# Funk.net
KiCad netlist of a schematic drawn in Altium Designer
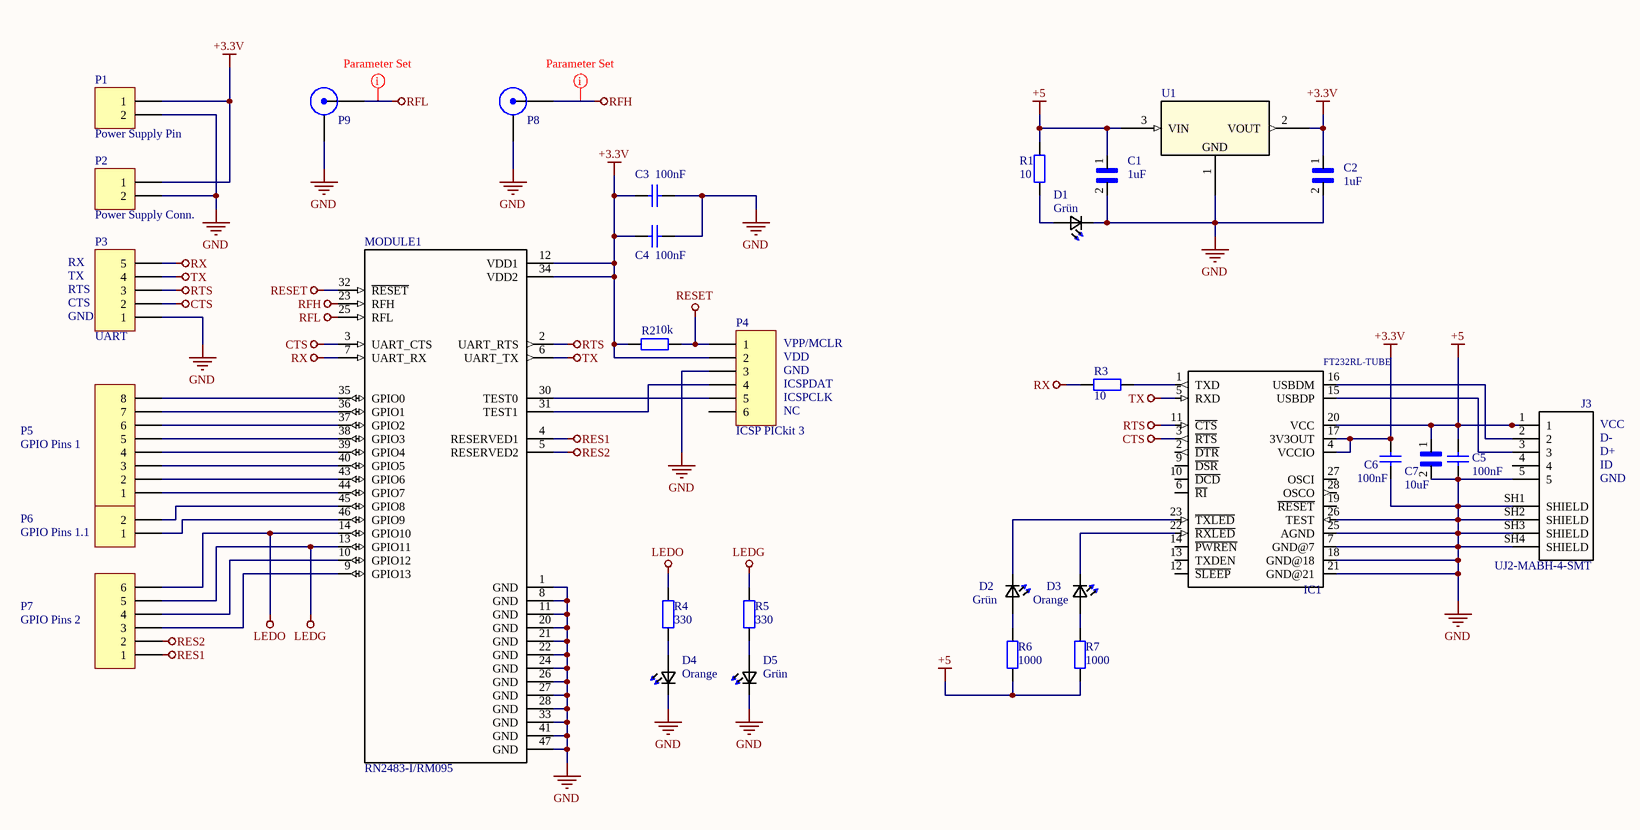
[diagram p0: Funk.SchDoc]

(export (version "E")
  (design (tool "Eeschema 10.0.6"))
  (components
    (comp (ref "C1")
      (value "1uF")
      (footprint "*CAPC2012X135N")
      (fields
        (field (name "DIGI-KEY_PART_NUMBER") "1276-6456-1-ND")
        (field (name "MP") "CL21A106KPFNNNG")
        (field (name "MF") "Samsung Electro-Mechanics")
      )
      (libsource (lib "Funk") (part "CL21A106KPFNNNG"))
    )
    (comp (ref "C2")
      (value "1uF")
      (footprint "*CAPC2012X135N")
      (fields
        (field (name "DIGI-KEY_PART_NUMBER") "1276-6456-1-ND")
        (field (name "MP") "CL21A106KPFNNNG")
        (field (name "MF") "Samsung Electro-Mechanics")
      )
      (libsource (lib "Funk") (part "CL21A106KPFNNNG"))
    )
    (comp (ref "C3")
      (value "100nF")
      (footprint "CAP_0603i_1608m -L")
      (description "capacitor")
      (libsource (lib "IDSC std generic parts") (part "Cap"))
    )
    (comp (ref "C4")
      (value "100nF")
      (footprint "CAP_0603i_1608m -L")
      (description "capacitor")
      (libsource (lib "IDSC std generic parts") (part "Cap"))
    )
    (comp (ref "C5")
      (value "100nF")
      (footprint "CAP_0603i_1608m -L")
      (description "capacitor")
      (libsource (lib "IDSC std generic parts") (part "Cap"))
    )
    (comp (ref "C6")
      (value "100nF")
      (footprint "CAP_0603i_1608m -L")
      (description "capacitor")
      (libsource (lib "IDSC std generic parts") (part "Cap"))
    )
    (comp (ref "C7")
      (value "10uF")
      (footprint "*CAPC2012X135N")
      (fields
        (field (name "DIGI-KEY_PART_NUMBER") "1276-6456-1-ND")
        (field (name "MP") "CL21A106KPFNNNG")
        (field (name "MF") "Samsung Electro-Mechanics")
      )
      (libsource (lib "Funk") (part "CL21A106KPFNNNG"))
    )
    (comp (ref "D1")
      (value "Grün")
      (footprint "*0603")
      (description "LED; SMD; 0603; gr黱; 35mcd; 1.6x0.8x0.55mm; 130掳; 2梅2.V; 20mA")
      (fields (field (name "MP") "LTST-C191KGKT") (field (name "DIGI-KEY_PART_NUMBER") "160-1446-1-ND"))
      (libsource (lib "Funk") (part "LTST-C191KGKT"))
    )
    (comp (ref "D2")
      (value "Grün")
      (footprint "*0603")
      (description "LED; SMD; 0603; gr黱; 35mcd; 1.6x0.8x0.55mm; 130掳; 2梅2.V; 20mA")
      (fields (field (name "MP") "LTST-C191KGKT") (field (name "DIGI-KEY_PART_NUMBER") "160-1446-1-ND"))
      (libsource (lib "Funk") (part "LTST-C191KGKT"))
    )
    (comp (ref "D3")
      (value "Orange")
      (footprint "*0603")
      (description "LED; SMD; 0603; orange; 45-90mcd; 1.6x0.8x0.55mm; 130Â°; 2Ã·2.4V; 20mA")
      (fields (field (name "MP") "LTST-C191KFKT") (field (name "DIGI-KEY_PART_NUMBER") "160-1445-1-ND"))
      (libsource (lib "Funk") (part "LTST-C191KFKT"))
    )
    (comp (ref "D4")
      (value "Orange")
      (footprint "*0603")
      (description "LED; SMD; 0603; orange; 45-90mcd; 1.6x0.8x0.55mm; 130Â°; 2Ã·2.4V; 20mA")
      (fields (field (name "MP") "LTST-C191KFKT") (field (name "DIGI-KEY_PART_NUMBER") "160-1445-1-ND"))
      (libsource (lib "Funk") (part "LTST-C191KFKT"))
    )
    (comp (ref "D5")
      (value "Grün")
      (footprint "*0603")
      (description "LED; SMD; 0603; gr黱; 35mcd; 1.6x0.8x0.55mm; 130掳; 2梅2.V; 20mA")
      (fields (field (name "MP") "LTST-C191KGKT") (field (name "DIGI-KEY_PART_NUMBER") "160-1446-1-ND"))
      (libsource (lib "Funk") (part "LTST-C191KGKT"))
    )
    (comp (ref "IC1")
      (value "FT232RL-TUBE")
      (footprint "*SSOP28-LD")
      (description "USB-to-UART 1-CH 256byte FIFO 5V 28-Pin SSOP Tube")
      (fields (field (name "DIGI-KEY_PART_NUMBER") "768-1306-ND") (field (name "MF") "FTDI,"))
      (libsource (lib "Funk") (part "FT232RL-TUBE"))
    )
    (comp (ref "J3")
      (value "UJ2-MABH-4-SMT")
      (footprint "*CUI_UJ2-MABH-4-SMT_UJ2-MABH-4-SMT(Primary)")
      (description "Mini AB, USB 2.0, 1 A, Right Angle, Surface Mount _SMT_, USB Receptacle")
      (fields (field (name "DIGI-KEY_PART_NUMBER") "102-5890-1-ND") (field (name "MF") "CUI Inc."))
      (libsource (lib "Funk") (part "UJ2-MABH-4-SMT"))
    )
    (comp (ref "MODULE1")
      (value "RN2483-I/RM095")
      (footprint "*MICROCHIP_RN2483-I/RM095")
      (description "Sub-GHz Dual Band Long Range Transceiver LoRa Module")
      (fields (field (name "MF") "Microchip"))
      (libsource (lib "Funk") (part "RN2483-I/RM095"))
    )
    (comp (ref "P1")
      (value "Power Supply Pin")
      (footprint "HDR1X2")
      (description "Header, 2-Pin")
      (libsource (lib "") (part "Header 2_1"))
    )
    (comp (ref "P2")
      (value "Power Supply Conn.")
      (footprint "3.5MM Phoenix Contact 1984617")
      (description "Header, 2-Pin")
      (libsource (lib "") (part "Header 2_1"))
    )
    (comp (ref "P3")
      (value "UART")
      (footprint "HDR1X5")
      (description "Header, 5-Pin")
      (libsource (lib "IDSC std connectors") (part "Header 5"))
    )
    (comp (ref "P4")
      (value "ICSP PICkit 3")
      (footprint "HDR1X6")
      (description "Header, 6-Pin")
      (libsource (lib "") (part "Header 6_1"))
    )
    (comp (ref "P5")
      (value "GPIO Pins 1")
      (footprint "HDR1X8")
      (description "Header, 8-Pin")
      (libsource (lib "IDSC std connectors") (part "Header 8"))
    )
    (comp (ref "P6")
      (value "GPIO Pins 1.1")
      (footprint "HDR1X2")
      (description "Header, 2-Pin")
      (libsource (lib "IDSC std connectors") (part "Header 2"))
    )
    (comp (ref "P7")
      (value "GPIO Pins 2")
      (footprint "HDR1X6")
      (description "Header, 6-Pin")
      (libsource (lib "IDSC std connectors") (part "Header 6"))
    )
    (comp (ref "P8")
      (value "Hirose U.FL-R-SMT-1(10)")
      (footprint "Hirsoe U.FL-R-SMT-1(10)")
      (description "U.FL")
      (libsource (lib "IDSC std connectors") (part "Hirose U.FL-R-SMT-1(10)"))
    )
    (comp (ref "P9")
      (value "Hirose U.FL-R-SMT-1(10)")
      (footprint "Hirsoe U.FL-R-SMT-1(10)")
      (description "U.FL")
      (libsource (lib "IDSC std connectors") (part "Hirose U.FL-R-SMT-1(10)"))
    )
    (comp (ref "R1")
      (value "10")
      (footprint "RES_0603i_1608m -N")
      (description "Resistor")
      (libsource (lib "") (part "Res_2"))
    )
    (comp (ref "R2")
      (value "10k")
      (footprint "RES_0603_1608m -L")
      (description "Resistor")
      (libsource (lib "") (part "Res_1"))
    )
    (comp (ref "R3")
      (value "10")
      (footprint "RES_0603i_1608m -N")
      (description "Resistor")
      (libsource (lib "") (part "Res_3"))
    )
    (comp (ref "R4")
      (value "330")
      (footprint "RES_0603i_1608m -N")
      (description "Resistor")
      (libsource (lib "IDSC std generic parts") (part "Res"))
    )
    (comp (ref "R5")
      (value "330")
      (footprint "RES_0603i_1608m -N")
      (description "Resistor")
      (libsource (lib "IDSC std generic parts") (part "Res"))
    )
    (comp (ref "R6")
      (value "1000")
      (footprint "RES_0603i_1608m -N")
      (description "Resistor")
      (libsource (lib "IDSC std generic parts") (part "Res"))
    )
    (comp (ref "R7")
      (value "1000")
      (footprint "RES_0603i_1608m -N")
      (description "Resistor")
      (libsource (lib "IDSC std generic parts") (part "Res"))
    )
    (comp (ref "U1")
      (value "Part Number: AP2120N-3.3TRG1")
      (footprint "SOT-23-M")
      (description "No Description Available")
      (fields
        (field (name "MANUFACTURER_PART_NUMBER") "AP2120N-3.3TRG1")
        (field (name "COPYRIGHT") "Copyright (C) 2018 Accelerated Designs. All rights reserved")
      )
      (libsource (lib "Funk") (part "AP2120N-3.3TRG1"))
    )
  )
  (nets
    (net (code "1") (name "+3.3V") (class "Default")
      (node (ref "C2") (pin "1") (pinfunction "1_1") (pintype "passive"))
      (node (ref "C3") (pin "2") (pinfunction "2_2") (pintype "passive"))
      (node (ref "C4") (pin "2") (pinfunction "2_2") (pintype "passive"))
      (node (ref "C6") (pin "2") (pinfunction "2_2") (pintype "passive"))
      (node (ref "IC1") (pin "17") (pinfunction "3V3OUT_17") (pintype "power_in"))
      (node (ref "IC1") (pin "4") (pinfunction "VCCIO_4") (pintype "power_in"))
      (node (ref "MODULE1") (pin "12") (pinfunction "VDD1_12") (pintype "power_in"))
      (node (ref "MODULE1") (pin "34") (pinfunction "VDD2_34") (pintype "power_in"))
      (node (ref "P1") (pin "1") (pinfunction "1_1") (pintype "passive"))
      (node (ref "P2") (pin "1") (pinfunction "1_1") (pintype "passive"))
      (node (ref "P4") (pin "2") (pinfunction "2_2") (pintype "passive"))
      (node (ref "R2") (pin "1") (pinfunction "1_1") (pintype "passive"))
      (node (ref "U1") (pin "2") (pinfunction "VOUT_2") (pintype "output"))
    )
    (net (code "2") (name "+5") (class "Default")
      (node (ref "C1") (pin "1") (pinfunction "1_1") (pintype "passive"))
      (node (ref "C5") (pin "2") (pinfunction "2_2") (pintype "passive"))
      (node (ref "C7") (pin "1") (pinfunction "1_1") (pintype "passive"))
      (node (ref "IC1") (pin "20") (pinfunction "VCC_20") (pintype "power_in"))
      (node (ref "J3") (pin "1") (pinfunction "1_1") (pintype "passive"))
      (node (ref "R1") (pin "1") (pinfunction "1_1") (pintype "passive"))
      (node (ref "R6") (pin "1") (pinfunction "1_1") (pintype "passive"))
      (node (ref "R7") (pin "1") (pinfunction "1_1") (pintype "passive"))
      (node (ref "U1") (pin "3") (pinfunction "VIN_3") (pintype "input"))
    )
    (net (code "3") (name "CTS") (class "Default")
      (node (ref "IC1") (pin "3") (pinfunction "~{RTS}_3") (pintype "output"))
      (node (ref "MODULE1") (pin "3") (pinfunction "UART_CTS_3") (pintype "input"))
      (node (ref "P3") (pin "2") (pinfunction "2_2") (pintype "passive"))
    )
    (net (code "4") (name "GND") (class "Default")
      (node (ref "C1") (pin "2") (pinfunction "2_2") (pintype "passive"))
      (node (ref "C2") (pin "2") (pinfunction "2_2") (pintype "passive"))
      (node (ref "C3") (pin "1") (pinfunction "1_1") (pintype "passive"))
      (node (ref "C4") (pin "1") (pinfunction "1_1") (pintype "passive"))
      (node (ref "C5") (pin "1") (pinfunction "1_1") (pintype "passive"))
      (node (ref "C6") (pin "1") (pinfunction "1_1") (pintype "passive"))
      (node (ref "C7") (pin "2") (pinfunction "2_2") (pintype "passive"))
      (node (ref "D1") (pin "1") (pinfunction "K2_1") (pintype "passive"))
      (node (ref "D4") (pin "1") (pinfunction "K2_1") (pintype "passive"))
      (node (ref "D5") (pin "1") (pinfunction "K2_1") (pintype "passive"))
      (node (ref "IC1") (pin "18") (pinfunction "GND@18_18") (pintype "power_in"))
      (node (ref "IC1") (pin "21") (pinfunction "GND@21_21") (pintype "power_in"))
      (node (ref "IC1") (pin "25") (pinfunction "AGND_25") (pintype "power_in"))
      (node (ref "IC1") (pin "26") (pinfunction "TEST_26") (pintype "input"))
      (node (ref "IC1") (pin "7") (pinfunction "GND@7_7") (pintype "power_in"))
      (node (ref "J3") (pin "5") (pinfunction "5_5") (pintype "passive"))
      (node (ref "J3") (pin "SH1") (pinfunction "SHIELD_SH1") (pintype "passive"))
      (node (ref "J3") (pin "SH2") (pinfunction "SHIELD_SH2") (pintype "passive"))
      (node (ref "J3") (pin "SH3") (pinfunction "SHIELD_SH3") (pintype "passive"))
      (node (ref "J3") (pin "SH4") (pinfunction "SHIELD_SH4") (pintype "passive"))
      (node (ref "MODULE1") (pin "1") (pinfunction "GND_1") (pintype "passive"))
      (node (ref "MODULE1") (pin "11") (pinfunction "GND_11") (pintype "passive"))
      (node (ref "MODULE1") (pin "20") (pinfunction "GND_20") (pintype "passive"))
      (node (ref "MODULE1") (pin "21") (pinfunction "GND_21") (pintype "passive"))
      (node (ref "MODULE1") (pin "22") (pinfunction "GND_22") (pintype "passive"))
      (node (ref "MODULE1") (pin "24") (pinfunction "GND_24") (pintype "passive"))
      (node (ref "MODULE1") (pin "26") (pinfunction "GND_26") (pintype "passive"))
      (node (ref "MODULE1") (pin "27") (pinfunction "GND_27") (pintype "passive"))
      (node (ref "MODULE1") (pin "28") (pinfunction "GND_28") (pintype "passive"))
      (node (ref "MODULE1") (pin "33") (pinfunction "GND_33") (pintype "passive"))
      (node (ref "MODULE1") (pin "41") (pinfunction "GND_41") (pintype "passive"))
      (node (ref "MODULE1") (pin "47") (pinfunction "GND_47") (pintype "passive"))
      (node (ref "MODULE1") (pin "8") (pinfunction "GND_8") (pintype "passive"))
      (node (ref "P1") (pin "2") (pinfunction "2_2") (pintype "passive"))
      (node (ref "P2") (pin "2") (pinfunction "2_2") (pintype "passive"))
      (node (ref "P3") (pin "1") (pinfunction "1_1") (pintype "passive"))
      (node (ref "P4") (pin "3") (pinfunction "3_3") (pintype "passive"))
      (node (ref "P8") (pin "2") (pinfunction "2_2") (pintype "passive"))
      (node (ref "P9") (pin "2") (pinfunction "2_2") (pintype "passive"))
      (node (ref "U1") (pin "1") (pinfunction "GND_1") (pintype "power_in"))
    )
    (net (code "5") (name "LEDG") (class "Default")
      (node (ref "MODULE1") (pin "13") (pinfunction "GPIO11_13") (pintype "bidirectional"))
      (node (ref "P7") (pin "5") (pinfunction "5_5") (pintype "passive"))
      (node (ref "R5") (pin "2") (pinfunction "2_2") (pintype "passive"))
    )
    (net (code "6") (name "LEDO") (class "Default")
      (node (ref "MODULE1") (pin "14") (pinfunction "GPIO10_14") (pintype "bidirectional"))
      (node (ref "P7") (pin "6") (pinfunction "6_6") (pintype "passive"))
      (node (ref "R4") (pin "2") (pinfunction "2_2") (pintype "passive"))
    )
    (net (code "7") (name "Net-(D1-A2)") (class "Default")
      (node (ref "D1") (pin "2") (pinfunction "A2_2") (pintype "passive"))
      (node (ref "R1") (pin "2") (pinfunction "2_2") (pintype "passive"))
    )
    (net (code "8") (name "Net-(D2-A2)") (class "Default")
      (node (ref "D2") (pin "2") (pinfunction "A2_2") (pintype "passive"))
      (node (ref "R6") (pin "2") (pinfunction "2_2") (pintype "passive"))
    )
    (net (code "9") (name "Net-(D2-K2)") (class "Default")
      (node (ref "D2") (pin "1") (pinfunction "K2_1") (pintype "passive"))
      (node (ref "IC1") (pin "23") (pinfunction "~{TXLED}_23") (pintype "input"))
    )
    (net (code "10") (name "Net-(D3-A2)") (class "Default")
      (node (ref "D3") (pin "2") (pinfunction "A2_2") (pintype "passive"))
      (node (ref "R7") (pin "2") (pinfunction "2_2") (pintype "passive"))
    )
    (net (code "11") (name "Net-(D3-K2)") (class "Default")
      (node (ref "D3") (pin "1") (pinfunction "K2_1") (pintype "passive"))
      (node (ref "IC1") (pin "22") (pinfunction "~{RXLED}_22") (pintype "input"))
    )
    (net (code "12") (name "Net-(D4-A2)") (class "Default")
      (node (ref "D4") (pin "2") (pinfunction "A2_2") (pintype "passive"))
      (node (ref "R4") (pin "1") (pinfunction "1_1") (pintype "passive"))
    )
    (net (code "13") (name "Net-(D5-A2)") (class "Default")
      (node (ref "D5") (pin "2") (pinfunction "A2_2") (pintype "passive"))
      (node (ref "R5") (pin "1") (pinfunction "1_1") (pintype "passive"))
    )
    (net (code "14") (name "Net-(IC1-TXD)") (class "Default")
      (node (ref "IC1") (pin "1") (pinfunction "TXD_1") (pintype "output"))
      (node (ref "R3") (pin "1") (pinfunction "1_1") (pintype "passive"))
    )
    (net (code "15") (name "Net-(IC1-USBDM)") (class "Default")
      (node (ref "IC1") (pin "16") (pinfunction "USBDM_16") (pintype "bidirectional"))
      (node (ref "J3") (pin "2") (pinfunction "2_2") (pintype "passive"))
    )
    (net (code "16") (name "Net-(IC1-USBDP)") (class "Default")
      (node (ref "IC1") (pin "15") (pinfunction "USBDP_15") (pintype "bidirectional"))
      (node (ref "J3") (pin "3") (pinfunction "3_3") (pintype "passive"))
    )
    (net (code "17") (name "Net-(MODULE1-GPIO0)") (class "Default")
      (node (ref "MODULE1") (pin "35") (pinfunction "GPIO0_35") (pintype "bidirectional"))
      (node (ref "P5") (pin "8") (pinfunction "8_8") (pintype "passive"))
    )
    (net (code "18") (name "Net-(MODULE1-GPIO1)") (class "Default")
      (node (ref "MODULE1") (pin "36") (pinfunction "GPIO1_36") (pintype "bidirectional"))
      (node (ref "P5") (pin "7") (pinfunction "7_7") (pintype "passive"))
    )
    (net (code "19") (name "Net-(MODULE1-GPIO2)") (class "Default")
      (node (ref "MODULE1") (pin "37") (pinfunction "GPIO2_37") (pintype "bidirectional"))
      (node (ref "P5") (pin "6") (pinfunction "6_6") (pintype "passive"))
    )
    (net (code "20") (name "Net-(MODULE1-GPIO3)") (class "Default")
      (node (ref "MODULE1") (pin "38") (pinfunction "GPIO3_38") (pintype "bidirectional"))
      (node (ref "P5") (pin "5") (pinfunction "5_5") (pintype "passive"))
    )
    (net (code "21") (name "Net-(MODULE1-GPIO4)") (class "Default")
      (node (ref "MODULE1") (pin "39") (pinfunction "GPIO4_39") (pintype "bidirectional"))
      (node (ref "P5") (pin "4") (pinfunction "4_4") (pintype "passive"))
    )
    (net (code "22") (name "Net-(MODULE1-GPIO5)") (class "Default")
      (node (ref "MODULE1") (pin "40") (pinfunction "GPIO5_40") (pintype "bidirectional"))
      (node (ref "P5") (pin "3") (pinfunction "3_3") (pintype "passive"))
    )
    (net (code "23") (name "Net-(MODULE1-GPIO6)") (class "Default")
      (node (ref "MODULE1") (pin "43") (pinfunction "GPIO6_43") (pintype "bidirectional"))
      (node (ref "P5") (pin "2") (pinfunction "2_2") (pintype "passive"))
    )
    (net (code "24") (name "Net-(MODULE1-GPIO7)") (class "Default")
      (node (ref "MODULE1") (pin "44") (pinfunction "GPIO7_44") (pintype "bidirectional"))
      (node (ref "P5") (pin "1") (pinfunction "1_1") (pintype "passive"))
    )
    (net (code "25") (name "Net-(MODULE1-GPIO8)") (class "Default")
      (node (ref "MODULE1") (pin "45") (pinfunction "GPIO8_45") (pintype "bidirectional"))
      (node (ref "P6") (pin "2") (pinfunction "2_2") (pintype "passive"))
    )
    (net (code "26") (name "Net-(MODULE1-GPIO9)") (class "Default")
      (node (ref "MODULE1") (pin "46") (pinfunction "GPIO9_46") (pintype "bidirectional"))
      (node (ref "P6") (pin "1") (pinfunction "1_1") (pintype "passive"))
    )
    (net (code "27") (name "Net-(MODULE1-GPIO12)") (class "Default")
      (node (ref "MODULE1") (pin "10") (pinfunction "GPIO12_10") (pintype "bidirectional"))
      (node (ref "P7") (pin "4") (pinfunction "4_4") (pintype "passive"))
    )
    (net (code "28") (name "Net-(MODULE1-GPIO13)") (class "Default")
      (node (ref "MODULE1") (pin "9") (pinfunction "GPIO13_9") (pintype "bidirectional"))
      (node (ref "P7") (pin "3") (pinfunction "3_3") (pintype "passive"))
    )
    (net (code "29") (name "Net-(MODULE1-TEST0)") (class "Default")
      (node (ref "MODULE1") (pin "30") (pinfunction "TEST0_30") (pintype "passive"))
      (node (ref "P4") (pin "5") (pinfunction "5_5") (pintype "passive"))
    )
    (net (code "30") (name "Net-(MODULE1-TEST1)") (class "Default")
      (node (ref "MODULE1") (pin "31") (pinfunction "TEST1_31") (pintype "passive"))
      (node (ref "P4") (pin "4") (pinfunction "4_4") (pintype "passive"))
    )
    (net (code "31") (name "RES1") (class "Default")
      (node (ref "MODULE1") (pin "4") (pinfunction "RESERVED1_4") (pintype "passive"))
      (node (ref "P7") (pin "1") (pinfunction "1_1") (pintype "passive"))
    )
    (net (code "32") (name "RES2") (class "Default")
      (node (ref "MODULE1") (pin "5") (pinfunction "RESERVED2_5") (pintype "passive"))
      (node (ref "P7") (pin "2") (pinfunction "2_2") (pintype "passive"))
    )
    (net (code "33") (name "RESET") (class "Default")
      (node (ref "MODULE1") (pin "32") (pinfunction "~{RESET}_32") (pintype "input"))
      (node (ref "P4") (pin "1") (pinfunction "1_1") (pintype "passive"))
      (node (ref "R2") (pin "2") (pinfunction "2_2") (pintype "passive"))
    )
    (net (code "34") (name "RFH") (class "Default")
      (node (ref "MODULE1") (pin "23") (pinfunction "RFH_23") (pintype "input"))
      (node (ref "P8") (pin "1") (pinfunction "1_1") (pintype "passive"))
    )
    (net (code "35") (name "RFL") (class "Default")
      (node (ref "MODULE1") (pin "25") (pinfunction "RFL_25") (pintype "input"))
      (node (ref "P9") (pin "1") (pinfunction "1_1") (pintype "passive"))
    )
    (net (code "36") (name "RTS") (class "Default")
      (node (ref "IC1") (pin "11") (pinfunction "~{CTS}_11") (pintype "input"))
      (node (ref "MODULE1") (pin "2") (pinfunction "UART_RTS_2") (pintype "output"))
      (node (ref "P3") (pin "3") (pinfunction "3_3") (pintype "passive"))
    )
    (net (code "37") (name "RX") (class "Default")
      (node (ref "MODULE1") (pin "7") (pinfunction "UART_RX_7") (pintype "input"))
      (node (ref "P3") (pin "5") (pinfunction "5_5") (pintype "passive"))
      (node (ref "R3") (pin "2") (pinfunction "2_2") (pintype "passive"))
    )
    (net (code "38") (name "TX") (class "Default")
      (node (ref "IC1") (pin "5") (pinfunction "RXD_5") (pintype "input"))
      (node (ref "MODULE1") (pin "6") (pinfunction "UART_TX_6") (pintype "output"))
      (node (ref "P3") (pin "4") (pinfunction "4_4") (pintype "passive"))
    )
    (net (code "39") (name "unconnected-(IC1-OSCI-Pad27)") (class "Default")
      (node (ref "IC1") (pin "27") (pinfunction "OSCI_27") (pintype "passive"))
    )
    (net (code "40") (name "unconnected-(IC1-OSCO-Pad28)") (class "Default")
      (node (ref "IC1") (pin "28") (pinfunction "OSCO_28") (pintype "output"))
    )
    (net (code "41") (name "unconnected-(IC1-TXDEN-Pad13)") (class "Default")
      (node (ref "IC1") (pin "13") (pinfunction "TXDEN_13") (pintype "passive"))
    )
    (net (code "42") (name "unconnected-(IC1-~{DCD}-Pad10)") (class "Default")
      (node (ref "IC1") (pin "10") (pinfunction "~{DCD}_10") (pintype "passive"))
    )
    (net (code "43") (name "unconnected-(IC1-~{DSR}-Pad9)") (class "Default")
      (node (ref "IC1") (pin "9") (pinfunction "~{DSR}_9") (pintype "passive"))
    )
    (net (code "44") (name "unconnected-(IC1-~{DTR}-Pad2)") (class "Default")
      (node (ref "IC1") (pin "2") (pinfunction "~{DTR}_2") (pintype "output"))
    )
    (net (code "45") (name "unconnected-(IC1-~{PWREN}-Pad14)") (class "Default")
      (node (ref "IC1") (pin "14") (pinfunction "~{PWREN}_14") (pintype "passive"))
    )
    (net (code "46") (name "unconnected-(IC1-~{RESET}-Pad19)") (class "Default")
      (node (ref "IC1") (pin "19") (pinfunction "~{RESET}_19") (pintype "passive"))
    )
    (net (code "47") (name "unconnected-(IC1-~{RI}-Pad6)") (class "Default")
      (node (ref "IC1") (pin "6") (pinfunction "~{RI}_6") (pintype "passive"))
    )
    (net (code "48") (name "unconnected-(IC1-~{SLEEP}-Pad12)") (class "Default")
      (node (ref "IC1") (pin "12") (pinfunction "~{SLEEP}_12") (pintype "passive"))
    )
    (net (code "49") (name "unconnected-(J3-Pad4)") (class "Default")
      (node (ref "J3") (pin "4") (pinfunction "4_4") (pintype "passive"))
    )
    (net (code "50") (name "unconnected-(P4-Pad6)") (class "Default")
      (node (ref "P4") (pin "6") (pinfunction "6_6") (pintype "passive"))
    )
  )
)
